# ADSB_Filter_LNA.net
KiCad netlist of a schematic drawn in EAGLE
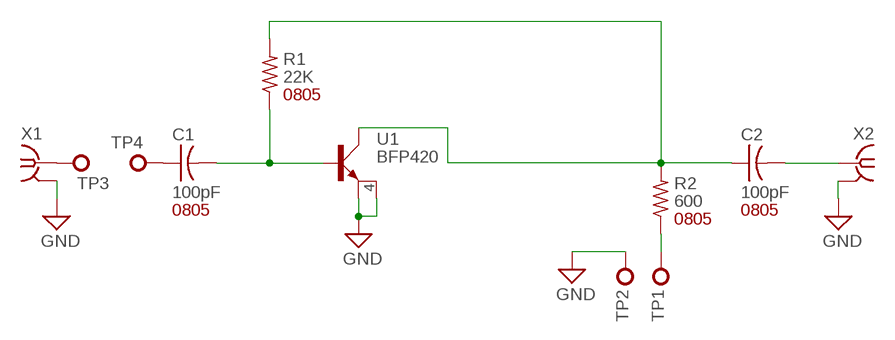
[diagram p0: schematic, sheet 1]

(export (version "E")
  (design (tool "Eeschema 10.0.6"))
  (components
    (comp (ref "C1")
      (value "100pF")
      (footprint "eagle-import:0805")
      (libsource (lib "eagle-import") (part "CAP0805"))
    )
    (comp (ref "C2")
      (value "100pF")
      (footprint "eagle-import:0805")
      (libsource (lib "eagle-import") (part "CAP0805"))
    )
    (comp (ref "R1")
      (value "22K")
      (footprint "eagle-import:0805")
      (libsource (lib "eagle-import") (part "RES0805"))
    )
    (comp (ref "R2")
      (value "600")
      (footprint "eagle-import:0805")
      (libsource (lib "eagle-import") (part "RES0805"))
    )
    (comp (ref "TP1")
      (value "TEST_POINTS76_150")
      (footprint "eagle-import:SMD_76_150")
      (libsource (lib "eagle-import") (part "TEST_POINTS76_150"))
    )
    (comp (ref "TP2")
      (value "TEST_POINTS76_150")
      (footprint "eagle-import:SMD_76_150")
      (libsource (lib "eagle-import") (part "TEST_POINTS76_150"))
    )
    (comp (ref "TP3")
      (value "TEST_POINTS8_8")
      (footprint "eagle-import:SMD_8_8")
      (libsource (lib "eagle-import") (part "TEST_POINTS8_8"))
    )
    (comp (ref "TP4")
      (value "TEST_POINTS8_8")
      (footprint "eagle-import:SMD_8_8")
      (libsource (lib "eagle-import") (part "TEST_POINTS8_8"))
    )
    (comp (ref "U1")
      (value "BFP420")
      (footprint "eagle-import:SOT343_INFINEON")
      (libsource (lib "eagle-import") (part "BFP420"))
    )
    (comp (ref "X1")
      (value "SMA-142-0701-801/806")
      (footprint "eagle-import:J502-ND-142-0701-801_806")
      (fields (field (name "MF") "JOHNSON COMPONENTS") (field (name "MPN") "142-0701-801"))
      (libsource (lib "eagle-import") (part "SMA-142-0701-801/806"))
    )
    (comp (ref "X2")
      (value "SMA-142-0701-801/806")
      (footprint "eagle-import:J502-ND-142-0701-801_806")
      (fields (field (name "MF") "JOHNSON COMPONENTS") (field (name "MPN") "142-0701-801"))
      (libsource (lib "eagle-import") (part "SMA-142-0701-801/806"))
    )
  )
  (nets
    (net (code "1") (name "GND") (class "Default")
      (node (ref "TP2") (pin "1") (pinfunction "MP_1") (pintype "passive"))
      (node (ref "U1") (pin "2") (pinfunction "E1_2") (pintype "passive"))
      (node (ref "U1") (pin "4") (pinfunction "E2_4") (pintype "passive"))
      (node (ref "X1") (pin "G@1") (pinfunction "GND_G@1") (pintype "power_in"))
      (node (ref "X2") (pin "G@1") (pinfunction "GND_G@1") (pintype "power_in"))
    )
    (net (code "2") (name "Net-(C2-Pad2)") (class "Default")
      (node (ref "C2") (pin "2") (pinfunction "2_2") (pintype "passive"))
      (node (ref "X2") (pin "1") (pinfunction "1_1") (pintype "passive"))
    )
    (net (code "3") (name "Net-(TP1-MP)") (class "Default")
      (node (ref "R2") (pin "1") (pinfunction "1_1") (pintype "passive"))
      (node (ref "TP1") (pin "1") (pinfunction "MP_1") (pintype "passive"))
    )
    (net (code "4") (name "Net-(TP3-MP)") (class "Default")
      (node (ref "TP3") (pin "1") (pinfunction "MP_1") (pintype "passive"))
      (node (ref "X1") (pin "1") (pinfunction "1_1") (pintype "passive"))
    )
    (net (code "5") (name "Net-(TP4-MP)") (class "Default")
      (node (ref "C1") (pin "1") (pinfunction "1_1") (pintype "passive"))
      (node (ref "TP4") (pin "1") (pinfunction "MP_1") (pintype "passive"))
    )
    (net (code "6") (name "Net-(U1-B)") (class "Default")
      (node (ref "C1") (pin "2") (pinfunction "2_2") (pintype "passive"))
      (node (ref "R1") (pin "1") (pinfunction "1_1") (pintype "passive"))
      (node (ref "U1") (pin "1") (pinfunction "B_1") (pintype "passive"))
    )
    (net (code "7") (name "Net-(U1-C)") (class "Default")
      (node (ref "C2") (pin "1") (pinfunction "1_1") (pintype "passive"))
      (node (ref "R1") (pin "2") (pinfunction "2_2") (pintype "passive"))
      (node (ref "R2") (pin "2") (pinfunction "2_2") (pintype "passive"))
      (node (ref "U1") (pin "3") (pinfunction "C_3") (pintype "passive"))
    )
  )
)
